# MCU.net
KiCad netlist of a schematic drawn in Altium Designer
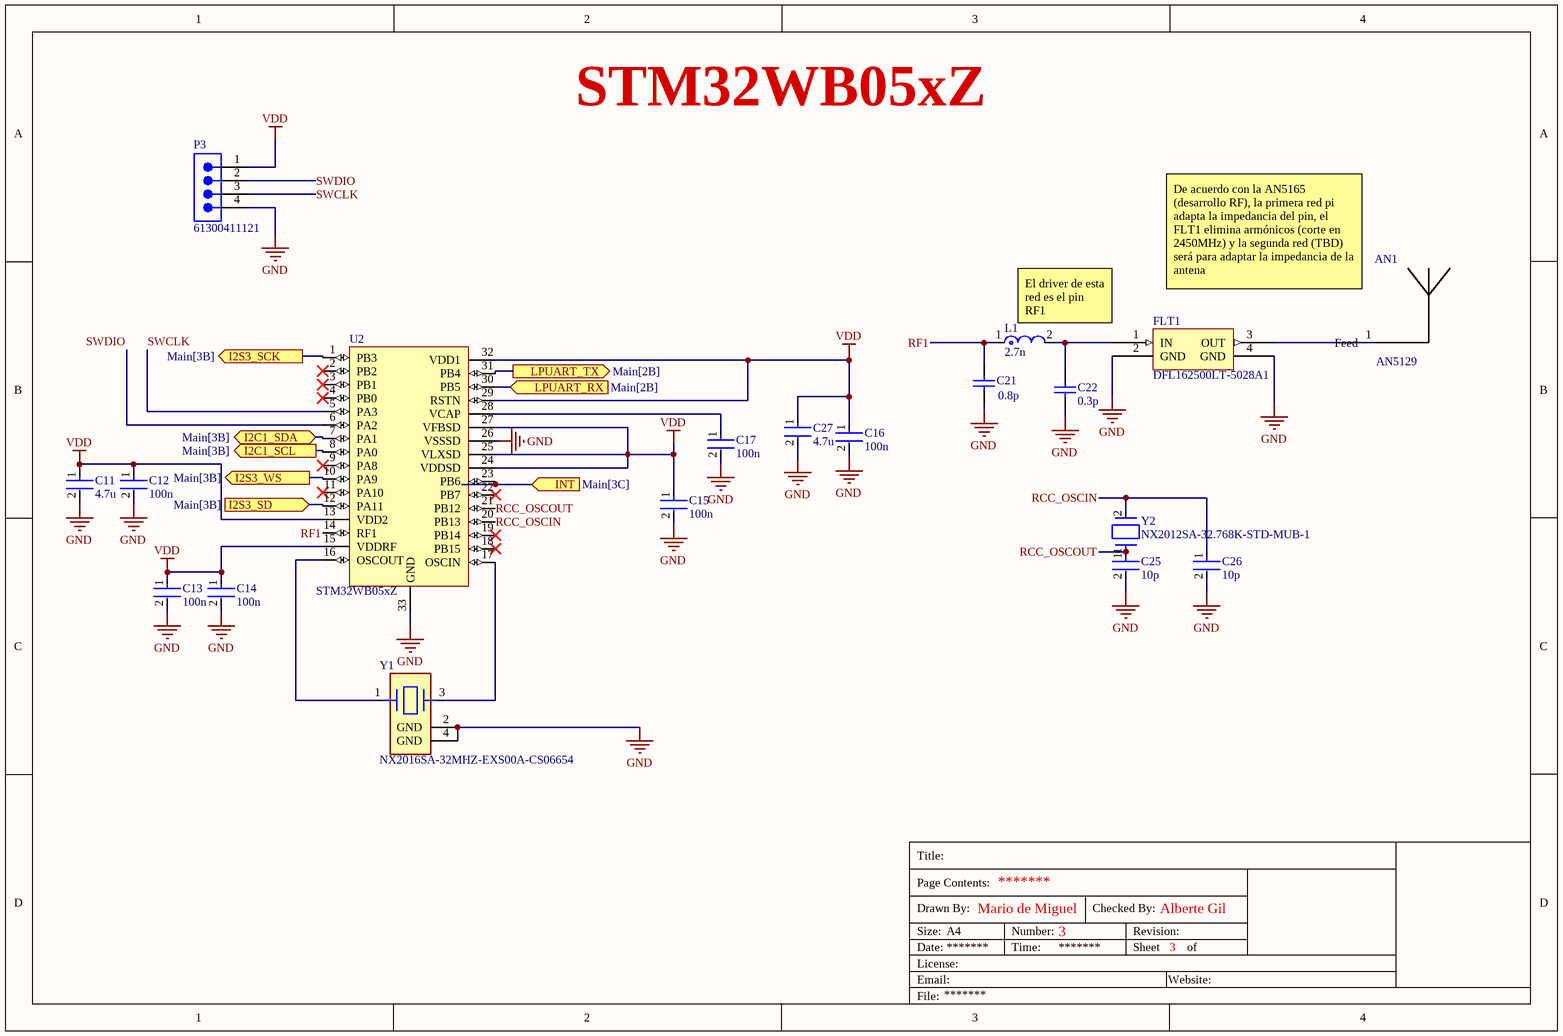
[diagram p0: MCU.SchDoc]

(export (version "E")
  (design (tool "Eeschema 10.0.6"))
  (components
    (comp (ref "AN1") (value "AN5129") (footprint "AN5129") (libsource (lib "DEOP2425") (part "AN5129")))
    (comp (ref "C11")
      (value "4.7u")
      (footprint "FP-GRM155-0_15-MFG")
      (description "Chip Multilayer Ceramic Capacitors for General Purpose, 0402, 4.7uF, X5R, 15%, 20%, 10V")
      (fields (field (name "TOLERANCE") "20%"))
      (libsource (lib "Altium Content Vault") (part "b4654b650e69147ec39a6b967a45e02"))
    )
    (comp (ref "C12")
      (value "100n")
      (footprint "FP-GRM033-0_03-MFG")
      (description "Chip Multilayer Ceramic Capacitors for General Purpose, 0201, 0.10uF, X7S, 22%, 10%, 16V")
      (fields (field (name "TOLERANCE") "10%"))
      (libsource (lib "Altium Content Vault") (part "b4654b650e69147ec39a6b967a45e02"))
    )
    (comp (ref "C13")
      (value "100n")
      (footprint "FP-GRM033-0_03-MFG")
      (description "Chip Multilayer Ceramic Capacitors for General Purpose, 0201, 0.10uF, X7S, 22%, 10%, 16V")
      (fields (field (name "TOLERANCE") "10%"))
      (libsource (lib "Altium Content Vault") (part "b4654b650e69147ec39a6b967a45e02"))
    )
    (comp (ref "C14")
      (value "100n")
      (footprint "FP-GRM033-0_03-MFG")
      (description "Chip Multilayer Ceramic Capacitors for General Purpose, 0201, 0.10uF, X7S, 22%, 10%, 16V")
      (fields (field (name "TOLERANCE") "10%"))
      (libsource (lib "Altium Content Vault") (part "b4654b650e69147ec39a6b967a45e02"))
    )
    (comp (ref "C15")
      (value "100n")
      (footprint "FP-GRM033-0_03-MFG")
      (description "Chip Multilayer Ceramic Capacitors for General Purpose, 0201, 0.10uF, X7S, 22%, 10%, 16V")
      (fields (field (name "TOLERANCE") "10%"))
      (libsource (lib "Altium Content Vault") (part "b4654b650e69147ec39a6b967a45e02"))
    )
    (comp (ref "C16")
      (value "100n")
      (footprint "FP-GRM033-0_03-MFG")
      (description "Chip Multilayer Ceramic Capacitors for General Purpose, 0201, 0.10uF, X7S, 22%, 10%, 16V")
      (fields (field (name "TOLERANCE") "10%"))
      (libsource (lib "Altium Content Vault") (part "b4654b650e69147ec39a6b967a45e02"))
    )
    (comp (ref "C17")
      (value "100n")
      (footprint "FP-GRM033-0_03-MFG")
      (description "Chip Multilayer Ceramic Capacitors for General Purpose, 0201, 0.10uF, X7S, 22%, 10%, 16V")
      (fields (field (name "TOLERANCE") "10%"))
      (libsource (lib "Altium Content Vault") (part "b4654b650e69147ec39a6b967a45e02"))
    )
    (comp (ref "C21")
      (value "0.8p")
      (footprint "CAPC1005X55X25LL05T10")
      (fields (field (name "PART NUMBER") "GRM1555C1HR80BA01D") (field (name "MANUFACTURER") "Murata"))
      (libsource (lib "Altium Content Vault") (part "CAP"))
    )
    (comp (ref "C22")
      (value "0.3p")
      (footprint "CAPC1005X55X25NL05T10")
      (fields (field (name "PART NUMBER") "GRM1555C1HR30WA01D") (field (name "MANUFACTURER") "Murata"))
      (libsource (lib "Altium Content Vault") (part "CAP"))
    )
    (comp (ref "C25")
      (value "10p")
      (footprint "FP-GRM033-0_03-IPC_A")
      (description "Chip Multilayer Ceramic Capacitors for General Purpose, 0201, 10pF, C0G, 30ppm/°C, 5%, 25V")
      (fields (field (name "TOLERANCE") "5%"))
      (libsource (lib "Altium Content Vault") (part "b4654b650e69147ec39a6b967a45e02"))
    )
    (comp (ref "C26")
      (value "10p")
      (footprint "FP-GRM033-0_03-IPC_A")
      (description "Chip Multilayer Ceramic Capacitors for General Purpose, 0201, 10pF, C0G, 30ppm/°C, 5%, 25V")
      (fields (field (name "TOLERANCE") "5%"))
      (libsource (lib "Altium Content Vault") (part "b4654b650e69147ec39a6b967a45e02"))
    )
    (comp (ref "C27")
      (value "4.7u")
      (footprint "FP-GRM155-0_15-MFG")
      (description "Chip Multilayer Ceramic Capacitors for General Purpose, 0402, 4.7uF, X5R, 15%, 20%, 10V")
      (fields (field (name "TOLERANCE") "20%"))
      (libsource (lib "Altium Content Vault") (part "b4654b650e69147ec39a6b967a45e02"))
    )
    (comp (ref "FLT1")
      (value "DFL162500LT-5028A1")
      (footprint "PCBComponent_1")
      (libsource (lib "filtrolp") (part "DFL162500LT-5028A1"))
    )
    (comp (ref "L1")
      (value "2.7n")
      (footprint "FP-LQG15HH_02-IPC_C")
      (description "Multilayer type RF Inductor 2.7nH ±0.3nH 0.12Ω 800mA 0402")
      (libsource (lib "Altium Content Vault") (part "4cc4b267dca4c8e51f7102f422741d8"))
    )
    (comp (ref "P3")
      (value "61300411121")
      (footprint "61300411121")
      (libsource (lib "Altium Content Vault") (part "Header_Male_1R_04P"))
    )
    (comp (ref "U2")
      (value "STM32WB05xZ")
      (footprint "STM32WB05XZ")
      (libsource (lib "DEOP2425") (part "STM32WB05xZ"))
    )
    (comp (ref "Y1")
      (value "NX2016SA-32MHZ-EXS00A-CS06654")
      (footprint "FP-NX2016SA-MFG")
      (description "CRYSTAL 32.0000MHZ 8PF SMD")
      (libsource (lib "Altium Content Vault") (part "0d11ad3ca7be055efd3b4f344707230"))
    )
    (comp (ref "Y2")
      (value "NX2012SA-32.768K-STD-MUB-1")
      (footprint "FP-NX2012SA-MFG")
      (description "CRYSTAL 32.7680KHZ 12.5PF SMD")
      (libsource (lib "Altium Content Vault") (part "c23a69dc6c9e2f18f2079038eb95dd1"))
    )
  )
  (nets
    (net (code "1") (name "/I2C1_SCL") (class "Default")
      (node (ref "U2") (pin "8") (pinfunction "PA0_8") (pintype "bidirectional"))
    )
    (net (code "2") (name "/I2C1_SDA") (class "Default")
      (node (ref "U2") (pin "7") (pinfunction "PA1_7") (pintype "bidirectional"))
    )
    (net (code "3") (name "/I2S3_SCK") (class "Default")
      (node (ref "U2") (pin "1") (pinfunction "PB3_1") (pintype "bidirectional"))
    )
    (net (code "4") (name "/I2S3_SD") (class "Default")
      (node (ref "U2") (pin "12") (pinfunction "PA11_12") (pintype "bidirectional"))
    )
    (net (code "5") (name "/I2S3_WS") (class "Default")
      (node (ref "U2") (pin "10") (pinfunction "PA9_10") (pintype "bidirectional"))
    )
    (net (code "6") (name "/INT") (class "Default")
      (node (ref "U2") (pin "23") (pinfunction "PB6_23") (pintype "bidirectional"))
    )
    (net (code "7") (name "/LPUART_RX") (class "Default")
      (node (ref "U2") (pin "30") (pinfunction "PB5_30") (pintype "bidirectional"))
    )
    (net (code "8") (name "/LPUART_TX") (class "Default")
      (node (ref "U2") (pin "31") (pinfunction "PB4_31") (pintype "bidirectional"))
    )
    (net (code "9") (name "/RCC_OSCIN") (class "Default")
      (node (ref "C26") (pin "1") (pinfunction "1_1") (pintype "passive"))
      (node (ref "U2") (pin "20") (pinfunction "PB13_20") (pintype "bidirectional"))
      (node (ref "Y2") (pin "2") (pinfunction "2_2") (pintype "passive"))
    )
    (net (code "10") (name "/RCC_OSCOUT") (class "Default")
      (node (ref "C25") (pin "1") (pinfunction "1_1") (pintype "passive"))
      (node (ref "U2") (pin "21") (pinfunction "PB12_21") (pintype "bidirectional"))
      (node (ref "Y2") (pin "1") (pinfunction "1_1") (pintype "passive"))
    )
    (net (code "11") (name "/RF1") (class "Default")
      (node (ref "C21") (pin "2") (pinfunction "2_2") (pintype "passive"))
      (node (ref "L1") (pin "1") (pinfunction "1_1") (pintype "passive"))
      (node (ref "U2") (pin "14") (pinfunction "RF1_14") (pintype "bidirectional"))
    )
    (net (code "12") (name "/SWCLK") (class "Default")
      (node (ref "P3") (pin "3") (pinfunction "3_3") (pintype "passive"))
      (node (ref "U2") (pin "5") (pinfunction "PA3_5") (pintype "bidirectional"))
    )
    (net (code "13") (name "/SWDIO") (class "Default")
      (node (ref "P3") (pin "2") (pinfunction "2_2") (pintype "passive"))
      (node (ref "U2") (pin "6") (pinfunction "PA2_6") (pintype "bidirectional"))
    )
    (net (code "14") (name "GND") (class "Default")
      (node (ref "C11") (pin "2") (pinfunction "2_2") (pintype "passive"))
      (node (ref "C12") (pin "2") (pinfunction "2_2") (pintype "passive"))
      (node (ref "C13") (pin "2") (pinfunction "2_2") (pintype "passive"))
      (node (ref "C14") (pin "2") (pinfunction "2_2") (pintype "passive"))
      (node (ref "C15") (pin "2") (pinfunction "2_2") (pintype "passive"))
      (node (ref "C16") (pin "2") (pinfunction "2_2") (pintype "passive"))
      (node (ref "C17") (pin "2") (pinfunction "2_2") (pintype "passive"))
      (node (ref "C21") (pin "1") (pinfunction "1_1") (pintype "passive"))
      (node (ref "C22") (pin "1") (pinfunction "1_1") (pintype "passive"))
      (node (ref "C25") (pin "2") (pinfunction "2_2") (pintype "passive"))
      (node (ref "C26") (pin "2") (pinfunction "2_2") (pintype "passive"))
      (node (ref "C27") (pin "2") (pinfunction "2_2") (pintype "passive"))
      (node (ref "FLT1") (pin "2") (pinfunction "GND_2") (pintype "power_in"))
      (node (ref "FLT1") (pin "4") (pinfunction "GND_4") (pintype "power_in"))
      (node (ref "P3") (pin "4") (pinfunction "4_4") (pintype "passive"))
      (node (ref "U2") (pin "26") (pinfunction "VSSSD_26") (pintype "power_in"))
      (node (ref "U2") (pin "33") (pinfunction "GND_33") (pintype "power_in"))
      (node (ref "Y1") (pin "2") (pinfunction "GND_2") (pintype "power_in"))
      (node (ref "Y1") (pin "4") (pinfunction "GND_4") (pintype "power_in"))
    )
    (net (code "15") (name "Net-(AN1-Feed)") (class "Default")
      (node (ref "AN1") (pin "1") (pinfunction "Feed_1") (pintype "passive"))
      (node (ref "FLT1") (pin "3") (pinfunction "OUT_3") (pintype "output"))
    )
    (net (code "16") (name "Net-(FLT1-IN)") (class "Default")
      (node (ref "C22") (pin "2") (pinfunction "2_2") (pintype "passive"))
      (node (ref "FLT1") (pin "1") (pinfunction "IN_1") (pintype "input"))
      (node (ref "L1") (pin "2") (pinfunction "2_2") (pintype "passive"))
    )
    (net (code "17") (name "Net-(U2-OSCIN)") (class "Default")
      (node (ref "U2") (pin "17") (pinfunction "OSCIN_17") (pintype "bidirectional"))
      (node (ref "Y1") (pin "3") (pinfunction "3_3") (pintype "passive"))
    )
    (net (code "18") (name "Net-(U2-OSCOUT)") (class "Default")
      (node (ref "U2") (pin "16") (pinfunction "OSCOUT_16") (pintype "bidirectional"))
      (node (ref "Y1") (pin "1") (pinfunction "1_1") (pintype "passive"))
    )
    (net (code "19") (name "Net-(U2-VCAP)") (class "Default")
      (node (ref "C17") (pin "1") (pinfunction "1_1") (pintype "passive"))
      (node (ref "U2") (pin "28") (pinfunction "VCAP_28") (pintype "power_in"))
    )
    (net (code "20") (name "VDD") (class "Default")
      (node (ref "C11") (pin "1") (pinfunction "1_1") (pintype "passive"))
      (node (ref "C12") (pin "1") (pinfunction "1_1") (pintype "passive"))
      (node (ref "C13") (pin "1") (pinfunction "1_1") (pintype "passive"))
      (node (ref "C14") (pin "1") (pinfunction "1_1") (pintype "passive"))
      (node (ref "C15") (pin "1") (pinfunction "1_1") (pintype "passive"))
      (node (ref "C16") (pin "1") (pinfunction "1_1") (pintype "passive"))
      (node (ref "C27") (pin "1") (pinfunction "1_1") (pintype "passive"))
      (node (ref "P3") (pin "1") (pinfunction "1_1") (pintype "passive"))
      (node (ref "U2") (pin "13") (pinfunction "VDD2_13") (pintype "power_in"))
      (node (ref "U2") (pin "15") (pinfunction "VDDRF_15") (pintype "power_in"))
      (node (ref "U2") (pin "24") (pinfunction "VDDSD_24") (pintype "power_in"))
      (node (ref "U2") (pin "25") (pinfunction "VLXSD_25") (pintype "power_in"))
      (node (ref "U2") (pin "27") (pinfunction "VFBSD_27") (pintype "power_in"))
      (node (ref "U2") (pin "29") (pinfunction "RSTN_29") (pintype "bidirectional"))
      (node (ref "U2") (pin "32") (pinfunction "VDD1_32") (pintype "power_in"))
    )
    (net (code "21") (name "unconnected-(U2-PA8-Pad9)") (class "Default")
      (node (ref "U2") (pin "9") (pinfunction "PA8_9") (pintype "bidirectional+no_connect"))
    )
    (net (code "22") (name "unconnected-(U2-PA10-Pad11)") (class "Default")
      (node (ref "U2") (pin "11") (pinfunction "PA10_11") (pintype "bidirectional+no_connect"))
    )
    (net (code "23") (name "unconnected-(U2-PB0-Pad4)") (class "Default")
      (node (ref "U2") (pin "4") (pinfunction "PB0_4") (pintype "bidirectional+no_connect"))
    )
    (net (code "24") (name "unconnected-(U2-PB1-Pad3)") (class "Default")
      (node (ref "U2") (pin "3") (pinfunction "PB1_3") (pintype "bidirectional+no_connect"))
    )
    (net (code "25") (name "unconnected-(U2-PB2-Pad2)") (class "Default")
      (node (ref "U2") (pin "2") (pinfunction "PB2_2") (pintype "bidirectional+no_connect"))
    )
    (net (code "26") (name "unconnected-(U2-PB7-Pad22)") (class "Default")
      (node (ref "U2") (pin "22") (pinfunction "PB7_22") (pintype "bidirectional+no_connect"))
    )
    (net (code "27") (name "unconnected-(U2-PB14-Pad19)") (class "Default")
      (node (ref "U2") (pin "19") (pinfunction "PB14_19") (pintype "bidirectional+no_connect"))
    )
    (net (code "28") (name "unconnected-(U2-PB15-Pad18)") (class "Default")
      (node (ref "U2") (pin "18") (pinfunction "PB15_18") (pintype "bidirectional+no_connect"))
    )
  )
)
